# 24V_to_1V8_1A_switching_regulator.net
KiCad netlist of a schematic drawn in EAGLE
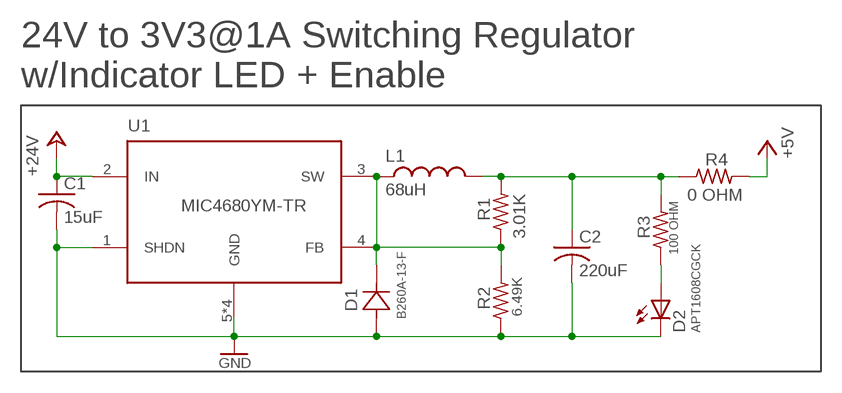
[diagram p0: schematic, sheet 1]

(export (version "E")
  (design (tool "Eeschema 10.0.6"))
  (components
    (comp (ref "C1")
      (value "15uF")
      (footprint "eagle-import:CT7343")
      (libsource (lib "eagle-import") (part "15UF-TPSD156K035R0100"))
    )
    (comp (ref "C2")
      (value "220uF")
      (footprint "eagle-import:CT7343")
      (libsource (lib "eagle-import") (part "220UF-TPSY227K010R0100"))
    )
    (comp (ref "D1")
      (value "B260A-13-F")
      (footprint "eagle-import:SMA")
      (libsource (lib "eagle-import") (part "B260A-13-F"))
    )
    (comp (ref "D2")
      (value "APT1608CGCK")
      (footprint "eagle-import:CHIPLED_0603")
      (libsource (lib "eagle-import") (part "APT1608CGCK"))
    )
    (comp (ref "L1")
      (value "68uH")
      (footprint "eagle-import:UP2B")
      (libsource (lib "eagle-import") (part "68UH-UP2B-680-R"))
    )
    (comp (ref "R1")
      (value "3.01K")
      (footprint "eagle-import:RC0603N")
      (libsource (lib "eagle-import") (part "3.01K-RC0603FR-073K01L"))
    )
    (comp (ref "R2")
      (value "6.49K")
      (footprint "eagle-import:RC0603N")
      (libsource (lib "eagle-import") (part "6.49K-RC0603FR-076K49L"))
    )
    (comp (ref "R3")
      (value "100 OHM")
      (footprint "eagle-import:RC0603N")
      (libsource (lib "eagle-import") (part "100OHM-RC0603JR-07100RL"))
    )
    (comp (ref "R4")
      (value "0 OHM")
      (footprint "eagle-import:RC0603N")
      (libsource (lib "eagle-import") (part "0OHM-RC0603JR-070RL"))
    )
    (comp (ref "U1")
      (value "MIC4680YM-TR")
      (footprint "eagle-import:SOIC8")
      (libsource (lib "eagle-import") (part "MIC4680YM-TR"))
    )
  )
  (nets
    (net (code "1") (name "+5V") (class "Default")
      (node (ref "R4") (pin "2") (pinfunction "2_2") (pintype "passive"))
    )
    (net (code "2") (name "+24V") (class "Default")
      (node (ref "C1") (pin "+") (pinfunction "1(+)_+") (pintype "passive"))
      (node (ref "U1") (pin "2") (pinfunction "IN_2") (pintype "bidirectional"))
    )
    (net (code "3") (name "GND") (class "Default")
      (node (ref "C1") (pin "-") (pinfunction "2(-)_-") (pintype "passive"))
      (node (ref "C2") (pin "-") (pinfunction "2(-)_-") (pintype "passive"))
      (node (ref "D1") (pin "2") (pinfunction "21_2") (pintype "passive"))
      (node (ref "D2") (pin "C") (pinfunction "C_C") (pintype "passive"))
      (node (ref "R2") (pin "1") (pinfunction "1_1") (pintype "passive"))
      (node (ref "U1") (pin "1") (pinfunction "SHDN_1") (pintype "bidirectional"))
      (node (ref "U1") (pin "5") (pinfunction "GND_5") (pintype "bidirectional"))
      (node (ref "U1") (pin "6") (pinfunction "GND_6") (pintype "bidirectional"))
      (node (ref "U1") (pin "7") (pinfunction "GND_7") (pintype "bidirectional"))
      (node (ref "U1") (pin "8") (pinfunction "GND_8") (pintype "bidirectional"))
    )
    (net (code "4") (name "Net-(C2-1(+))") (class "Default")
      (node (ref "C2") (pin "+") (pinfunction "1(+)_+") (pintype "passive"))
      (node (ref "L1") (pin "2") (pinfunction "2_2") (pintype "passive"))
      (node (ref "R1") (pin "2") (pinfunction "2_2") (pintype "passive"))
      (node (ref "R3") (pin "2") (pinfunction "2_2") (pintype "passive"))
      (node (ref "R4") (pin "1") (pinfunction "1_1") (pintype "passive"))
    )
    (net (code "5") (name "Net-(D1-12)") (class "Default")
      (node (ref "D1") (pin "1") (pinfunction "12_1") (pintype "passive"))
      (node (ref "L1") (pin "1") (pinfunction "1_1") (pintype "passive"))
      (node (ref "R1") (pin "1") (pinfunction "1_1") (pintype "passive"))
      (node (ref "R2") (pin "2") (pinfunction "2_2") (pintype "passive"))
      (node (ref "U1") (pin "3") (pinfunction "SW_3") (pintype "bidirectional"))
      (node (ref "U1") (pin "4") (pinfunction "FB_4") (pintype "bidirectional"))
    )
    (net (code "6") (name "Net-(D2-PadA)") (class "Default")
      (node (ref "D2") (pin "A") (pinfunction "A_A") (pintype "passive"))
      (node (ref "R3") (pin "1") (pinfunction "1_1") (pintype "passive"))
    )
  )
)
